# ARE_adaptadora_AT90-8535_40pin.net
KiCad netlist of a schematic drawn in EAGLE
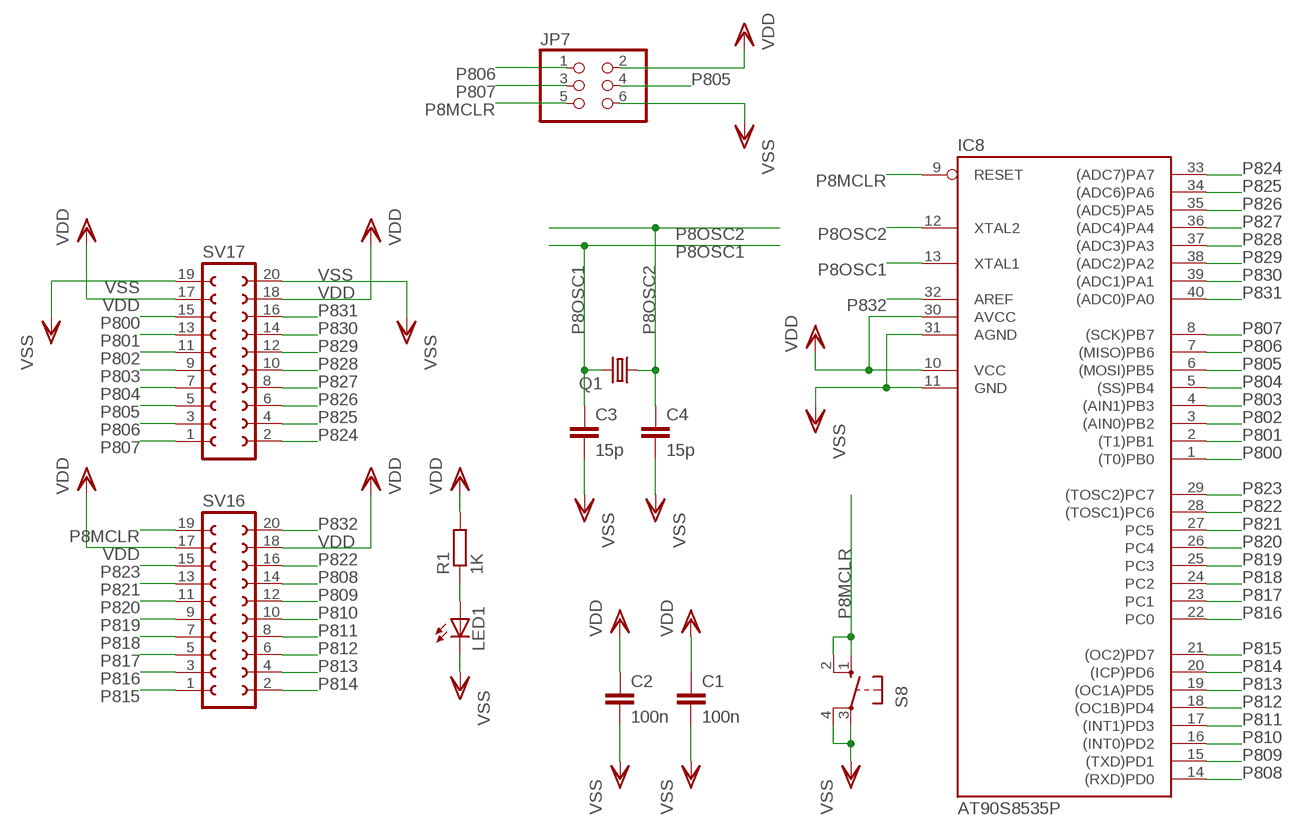
[diagram p0: schematic, sheet 1]

(export (version "E")
  (design (tool "Eeschema 10.0.6"))
  (components
    (comp (ref "C1")
      (value "100n")
      (footprint "eagle-import:C0805")
      (libsource (lib "eagle-import") (part "C-EUC0805"))
    )
    (comp (ref "C2")
      (value "100n")
      (footprint "eagle-import:C0805")
      (libsource (lib "eagle-import") (part "C-EUC0805"))
    )
    (comp (ref "C3")
      (value "15p")
      (footprint "eagle-import:C0805")
      (libsource (lib "eagle-import") (part "C-EUC0805"))
    )
    (comp (ref "C4")
      (value "15p")
      (footprint "eagle-import:C0805")
      (libsource (lib "eagle-import") (part "C-EUC0805"))
    )
    (comp (ref "IC8")
      (value "AT90S8535P")
      (footprint "eagle-import:DIL40")
      (libsource (lib "eagle-import") (part "AT908535PS"))
    )
    (comp (ref "JP7")
      (value "PINHD-2X3")
      (footprint "eagle-import:2X03")
      (libsource (lib "eagle-import") (part "PINHD-2X3"))
    )
    (comp (ref "LED1")
      (value "LED3MM")
      (footprint "eagle-import:LED3MM")
      (libsource (lib "eagle-import") (part "LED3MM"))
    )
    (comp (ref "Q1")
      (value "CRYSTALHC18U-V")
      (footprint "eagle-import:HC18U-V")
      (libsource (lib "eagle-import") (part "CRYSTALHC18U-V"))
    )
    (comp (ref "R1")
      (value "1K")
      (footprint "eagle-import:R0805")
      (libsource (lib "eagle-import") (part "R-EU_R0805"))
    )
    (comp (ref "S8")
      (value "10-XX")
      (footprint "eagle-import:B3F-10XX")
      (fields
        (field (name "MPN") "B3F-1000")
        (field (name "MPN_1") "B3F-1000")
        (field (name "OC_FARNELL") "176432")
        (field (name "OC_NEWARK") "36M3542")
      )
      (libsource (lib "eagle-import") (part "10-XX"))
    )
    (comp (ref "SV16")
      (value "FE10-2W")
      (footprint "eagle-import:FE10-2W")
      (libsource (lib "eagle-import") (part "FE10-2W"))
    )
    (comp (ref "SV17")
      (value "FE10-2W")
      (footprint "eagle-import:FE10-2W")
      (libsource (lib "eagle-import") (part "FE10-2W"))
    )
  )
  (nets
    (net (code "1") (name "/P8MCLR") (class "Default")
      (node (ref "IC8") (pin "9") (pinfunction "RESET_9") (pintype "input"))
      (node (ref "JP7") (pin "5") (pinfunction "5_5") (pintype "passive"))
      (node (ref "S8") (pin "1") (pinfunction "S_1") (pintype "passive"))
      (node (ref "S8") (pin "2") (pinfunction "S1_2") (pintype "passive"))
      (node (ref "SV16") (pin "19") (pinfunction "19_19") (pintype "passive"))
    )
    (net (code "2") (name "/P8OSC1") (class "Default")
      (node (ref "C3") (pin "1") (pinfunction "1_1") (pintype "passive"))
      (node (ref "IC8") (pin "13") (pinfunction "XTAL1_13") (pintype "bidirectional"))
      (node (ref "Q1") (pin "2") (pinfunction "2_2") (pintype "passive"))
    )
    (net (code "3") (name "/P8OSC2") (class "Default")
      (node (ref "C4") (pin "1") (pinfunction "1_1") (pintype "passive"))
      (node (ref "IC8") (pin "12") (pinfunction "XTAL2_12") (pintype "bidirectional"))
      (node (ref "Q1") (pin "1") (pinfunction "1_1") (pintype "passive"))
    )
    (net (code "4") (name "/P800") (class "Default")
      (node (ref "IC8") (pin "1") (pinfunction "(T0)PB0_1") (pintype "bidirectional"))
      (node (ref "SV17") (pin "15") (pinfunction "15_15") (pintype "passive"))
    )
    (net (code "5") (name "/P801") (class "Default")
      (node (ref "IC8") (pin "2") (pinfunction "(T1)PB1_2") (pintype "bidirectional"))
      (node (ref "SV17") (pin "13") (pinfunction "13_13") (pintype "passive"))
    )
    (net (code "6") (name "/P802") (class "Default")
      (node (ref "IC8") (pin "3") (pinfunction "(AIN0)PB2_3") (pintype "bidirectional"))
      (node (ref "SV17") (pin "11") (pinfunction "11_11") (pintype "passive"))
    )
    (net (code "7") (name "/P803") (class "Default")
      (node (ref "IC8") (pin "4") (pinfunction "(AIN1)PB3_4") (pintype "bidirectional"))
      (node (ref "SV17") (pin "9") (pinfunction "9_9") (pintype "passive"))
    )
    (net (code "8") (name "/P804") (class "Default")
      (node (ref "IC8") (pin "5") (pinfunction "(SS)PB4_5") (pintype "bidirectional"))
      (node (ref "SV17") (pin "7") (pinfunction "7_7") (pintype "passive"))
    )
    (net (code "9") (name "/P805") (class "Default")
      (node (ref "IC8") (pin "6") (pinfunction "(MOSI)PB5_6") (pintype "bidirectional"))
      (node (ref "JP7") (pin "4") (pinfunction "4_4") (pintype "passive"))
      (node (ref "SV17") (pin "5") (pinfunction "5_5") (pintype "passive"))
    )
    (net (code "10") (name "/P806") (class "Default")
      (node (ref "IC8") (pin "7") (pinfunction "(MISO)PB6_7") (pintype "bidirectional"))
      (node (ref "JP7") (pin "1") (pinfunction "1_1") (pintype "passive"))
      (node (ref "SV17") (pin "3") (pinfunction "3_3") (pintype "passive"))
    )
    (net (code "11") (name "/P807") (class "Default")
      (node (ref "IC8") (pin "8") (pinfunction "(SCK)PB7_8") (pintype "bidirectional"))
      (node (ref "JP7") (pin "3") (pinfunction "3_3") (pintype "passive"))
      (node (ref "SV17") (pin "1") (pinfunction "1_1") (pintype "passive"))
    )
    (net (code "12") (name "/P808") (class "Default")
      (node (ref "IC8") (pin "14") (pinfunction "(RXD)PD0_14") (pintype "bidirectional"))
      (node (ref "SV16") (pin "14") (pinfunction "14_14") (pintype "passive"))
    )
    (net (code "13") (name "/P809") (class "Default")
      (node (ref "IC8") (pin "15") (pinfunction "(TXD)PD1_15") (pintype "bidirectional"))
      (node (ref "SV16") (pin "12") (pinfunction "12_12") (pintype "passive"))
    )
    (net (code "14") (name "/P810") (class "Default")
      (node (ref "IC8") (pin "16") (pinfunction "(INT0)PD2_16") (pintype "bidirectional"))
      (node (ref "SV16") (pin "10") (pinfunction "10_10") (pintype "passive"))
    )
    (net (code "15") (name "/P811") (class "Default")
      (node (ref "IC8") (pin "17") (pinfunction "(INT1)PD3_17") (pintype "bidirectional"))
      (node (ref "SV16") (pin "8") (pinfunction "8_8") (pintype "passive"))
    )
    (net (code "16") (name "/P812") (class "Default")
      (node (ref "IC8") (pin "18") (pinfunction "(OC1B)PD4_18") (pintype "bidirectional"))
      (node (ref "SV16") (pin "6") (pinfunction "6_6") (pintype "passive"))
    )
    (net (code "17") (name "/P813") (class "Default")
      (node (ref "IC8") (pin "19") (pinfunction "(OC1A)PD5_19") (pintype "bidirectional"))
      (node (ref "SV16") (pin "4") (pinfunction "4_4") (pintype "passive"))
    )
    (net (code "18") (name "/P814") (class "Default")
      (node (ref "IC8") (pin "20") (pinfunction "(ICP)PD6_20") (pintype "bidirectional"))
      (node (ref "SV16") (pin "2") (pinfunction "2_2") (pintype "passive"))
    )
    (net (code "19") (name "/P815") (class "Default")
      (node (ref "IC8") (pin "21") (pinfunction "(OC2)PD7_21") (pintype "bidirectional"))
      (node (ref "SV16") (pin "1") (pinfunction "1_1") (pintype "passive"))
    )
    (net (code "20") (name "/P816") (class "Default")
      (node (ref "IC8") (pin "22") (pinfunction "PC0_22") (pintype "bidirectional"))
      (node (ref "SV16") (pin "3") (pinfunction "3_3") (pintype "passive"))
    )
    (net (code "21") (name "/P817") (class "Default")
      (node (ref "IC8") (pin "23") (pinfunction "PC1_23") (pintype "bidirectional"))
      (node (ref "SV16") (pin "5") (pinfunction "5_5") (pintype "passive"))
    )
    (net (code "22") (name "/P818") (class "Default")
      (node (ref "IC8") (pin "24") (pinfunction "PC2_24") (pintype "bidirectional"))
      (node (ref "SV16") (pin "7") (pinfunction "7_7") (pintype "passive"))
    )
    (net (code "23") (name "/P819") (class "Default")
      (node (ref "IC8") (pin "25") (pinfunction "PC3_25") (pintype "bidirectional"))
      (node (ref "SV16") (pin "9") (pinfunction "9_9") (pintype "passive"))
    )
    (net (code "24") (name "/P820") (class "Default")
      (node (ref "IC8") (pin "26") (pinfunction "PC4_26") (pintype "bidirectional"))
      (node (ref "SV16") (pin "11") (pinfunction "11_11") (pintype "passive"))
    )
    (net (code "25") (name "/P821") (class "Default")
      (node (ref "IC8") (pin "27") (pinfunction "PC5_27") (pintype "bidirectional"))
      (node (ref "SV16") (pin "13") (pinfunction "13_13") (pintype "passive"))
    )
    (net (code "26") (name "/P822") (class "Default")
      (node (ref "IC8") (pin "28") (pinfunction "(TOSC1)PC6_28") (pintype "bidirectional"))
      (node (ref "SV16") (pin "16") (pinfunction "16_16") (pintype "passive"))
    )
    (net (code "27") (name "/P823") (class "Default")
      (node (ref "IC8") (pin "29") (pinfunction "(TOSC2)PC7_29") (pintype "bidirectional"))
      (node (ref "SV16") (pin "15") (pinfunction "15_15") (pintype "passive"))
    )
    (net (code "28") (name "/P824") (class "Default")
      (node (ref "IC8") (pin "33") (pinfunction "(ADC7)PA7_33") (pintype "bidirectional"))
      (node (ref "SV17") (pin "2") (pinfunction "2_2") (pintype "passive"))
    )
    (net (code "29") (name "/P825") (class "Default")
      (node (ref "IC8") (pin "34") (pinfunction "(ADC6)PA6_34") (pintype "bidirectional"))
      (node (ref "SV17") (pin "4") (pinfunction "4_4") (pintype "passive"))
    )
    (net (code "30") (name "/P826") (class "Default")
      (node (ref "IC8") (pin "35") (pinfunction "(ADC5)PA5_35") (pintype "bidirectional"))
      (node (ref "SV17") (pin "6") (pinfunction "6_6") (pintype "passive"))
    )
    (net (code "31") (name "/P827") (class "Default")
      (node (ref "IC8") (pin "36") (pinfunction "(ADC4)PA4_36") (pintype "bidirectional"))
      (node (ref "SV17") (pin "8") (pinfunction "8_8") (pintype "passive"))
    )
    (net (code "32") (name "/P828") (class "Default")
      (node (ref "IC8") (pin "37") (pinfunction "(ADC3)PA3_37") (pintype "bidirectional"))
      (node (ref "SV17") (pin "10") (pinfunction "10_10") (pintype "passive"))
    )
    (net (code "33") (name "/P829") (class "Default")
      (node (ref "IC8") (pin "38") (pinfunction "(ADC2)PA2_38") (pintype "bidirectional"))
      (node (ref "SV17") (pin "12") (pinfunction "12_12") (pintype "passive"))
    )
    (net (code "34") (name "/P830") (class "Default")
      (node (ref "IC8") (pin "39") (pinfunction "(ADC1)PA1_39") (pintype "bidirectional"))
      (node (ref "SV17") (pin "14") (pinfunction "14_14") (pintype "passive"))
    )
    (net (code "35") (name "/P831") (class "Default")
      (node (ref "IC8") (pin "40") (pinfunction "(ADC0)PA0_40") (pintype "bidirectional"))
      (node (ref "SV17") (pin "16") (pinfunction "16_16") (pintype "passive"))
    )
    (net (code "36") (name "/P832") (class "Default")
      (node (ref "IC8") (pin "32") (pinfunction "AREF_32") (pintype "passive"))
      (node (ref "SV16") (pin "20") (pinfunction "20_20") (pintype "passive"))
    )
    (net (code "37") (name "Net-(LED1-PadA)") (class "Default")
      (node (ref "LED1") (pin "A") (pinfunction "A_A") (pintype "passive"))
      (node (ref "R1") (pin "1") (pinfunction "1_1") (pintype "passive"))
    )
    (net (code "38") (name "VDD") (class "Default")
      (node (ref "C1") (pin "1") (pinfunction "1_1") (pintype "passive"))
      (node (ref "C2") (pin "1") (pinfunction "1_1") (pintype "passive"))
      (node (ref "IC8") (pin "10") (pinfunction "VCC_10") (pintype "power_in"))
      (node (ref "IC8") (pin "30") (pinfunction "AVCC_30") (pintype "power_in"))
      (node (ref "JP7") (pin "2") (pinfunction "2_2") (pintype "passive"))
      (node (ref "R1") (pin "2") (pinfunction "2_2") (pintype "passive"))
      (node (ref "SV16") (pin "17") (pinfunction "17_17") (pintype "passive"))
      (node (ref "SV16") (pin "18") (pinfunction "18_18") (pintype "passive"))
      (node (ref "SV17") (pin "17") (pinfunction "17_17") (pintype "passive"))
      (node (ref "SV17") (pin "18") (pinfunction "18_18") (pintype "passive"))
    )
    (net (code "39") (name "VSS") (class "Default")
      (node (ref "C1") (pin "2") (pinfunction "2_2") (pintype "passive"))
      (node (ref "C2") (pin "2") (pinfunction "2_2") (pintype "passive"))
      (node (ref "C3") (pin "2") (pinfunction "2_2") (pintype "passive"))
      (node (ref "C4") (pin "2") (pinfunction "2_2") (pintype "passive"))
      (node (ref "IC8") (pin "11") (pinfunction "GND_11") (pintype "power_in"))
      (node (ref "IC8") (pin "31") (pinfunction "AGND_31") (pintype "power_in"))
      (node (ref "JP7") (pin "6") (pinfunction "6_6") (pintype "passive"))
      (node (ref "LED1") (pin "K") (pinfunction "C_K") (pintype "passive"))
      (node (ref "S8") (pin "3") (pinfunction "P_3") (pintype "passive"))
      (node (ref "S8") (pin "4") (pinfunction "P1_4") (pintype "passive"))
      (node (ref "SV17") (pin "19") (pinfunction "19_19") (pintype "passive"))
      (node (ref "SV17") (pin "20") (pinfunction "20_20") (pintype "passive"))
    )
  )
)
